# attinier84-2digit-shield-mk-1_0.net
KiCad netlist of a schematic drawn in EAGLE
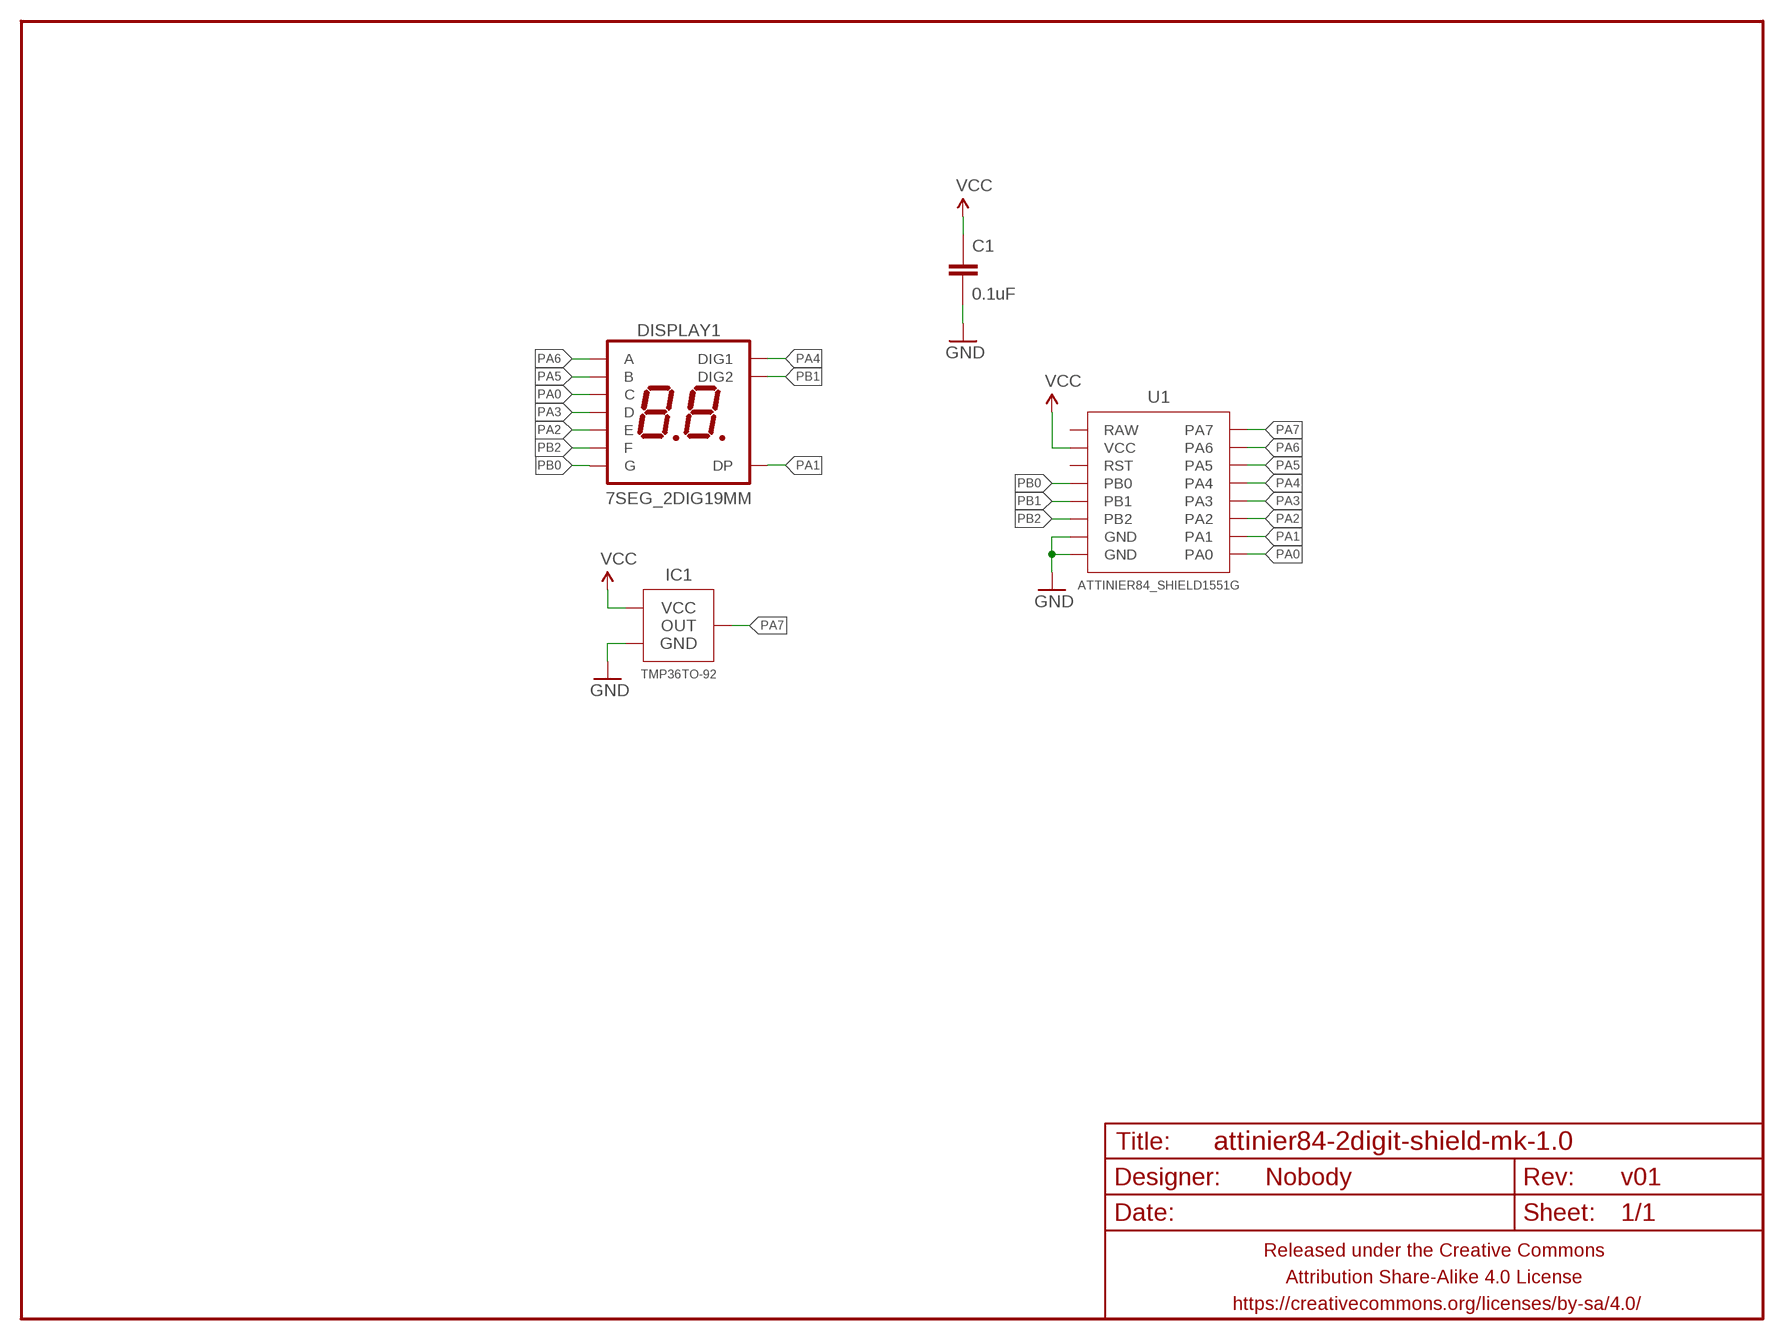
[diagram p0: schematic, sheet 1]

(export (version "E")
  (design (tool "Eeschema 10.0.6"))
  (components
    (comp (ref "C1")
      (value "0.1uF")
      (footprint "eagle-import:C025-024X044")
      (libsource (lib "eagle-import") (part "CAPACITOR-CERAMIC025-024X044"))
    )
    (comp (ref "DISPLAY1")
      (value "7SEG_2DIG19MM")
      (footprint "eagle-import:7SEG_2DIG_19MM")
      (libsource (lib "eagle-import") (part "7SEG_2DIG19MM"))
    )
    (comp (ref "FRAME1")
      (value "FRAME-LETTERNO_PACKAGE")
      (footprint "eagle-import:DUMMY")
      (fields (field (name "DESIGNER") "Nobody"))
      (libsource (lib "eagle-import") (part "FRAME-LETTERNO_PACKAGE"))
    )
    (comp (ref "IC1")
      (value "TMP36TO-92")
      (footprint "eagle-import:TO-92-AMMO")
      (libsource (lib "eagle-import") (part "TMP36TO-92"))
    )
    (comp (ref "U1")
      (value "ATTINIER84_SHIELD1551G")
      (footprint "eagle-import:ATTINIER84_SHIELD2")
      (libsource (lib "eagle-import") (part "ATTINIER84_SHIELD1551G"))
    )
  )
  (nets
    (net (code "1") (name "GND") (class "Default")
      (node (ref "C1") (pin "2") (pinfunction "2_2") (pintype "passive"))
      (node (ref "IC1") (pin "3") (pinfunction "GND_3") (pintype "bidirectional"))
      (node (ref "U1") (pin "GND@1") (pinfunction "GND_GND@1") (pintype "bidirectional"))
      (node (ref "U1") (pin "GND@2") (pinfunction "GND_GND@2") (pintype "bidirectional"))
    )
    (net (code "2") (name "PA0") (class "Default")
      (node (ref "DISPLAY1") (pin "1") (pinfunction "C_1") (pintype "passive"))
      (node (ref "U1") (pin "PA0") (pinfunction "PA0_PA0") (pintype "bidirectional"))
    )
    (net (code "3") (name "PA1") (class "Default")
      (node (ref "DISPLAY1") (pin "2") (pinfunction "DP_2") (pintype "passive"))
      (node (ref "U1") (pin "PA1") (pinfunction "PA1_PA1") (pintype "bidirectional"))
    )
    (net (code "4") (name "PA2") (class "Default")
      (node (ref "DISPLAY1") (pin "3") (pinfunction "E_3") (pintype "passive"))
      (node (ref "U1") (pin "PA2") (pinfunction "PA2_PA2") (pintype "bidirectional"))
    )
    (net (code "5") (name "PA3") (class "Default")
      (node (ref "DISPLAY1") (pin "4") (pinfunction "D_4") (pintype "passive"))
      (node (ref "U1") (pin "PA3") (pinfunction "PA3_PA3") (pintype "bidirectional"))
    )
    (net (code "6") (name "PA4") (class "Default")
      (node (ref "DISPLAY1") (pin "8") (pinfunction "DIG1_8") (pintype "passive"))
      (node (ref "U1") (pin "PA4") (pinfunction "PA4_PA4") (pintype "bidirectional"))
    )
    (net (code "7") (name "PA5") (class "Default")
      (node (ref "DISPLAY1") (pin "9") (pinfunction "B_9") (pintype "passive"))
      (node (ref "U1") (pin "PA5") (pinfunction "PA5_PA5") (pintype "bidirectional"))
    )
    (net (code "8") (name "PA6") (class "Default")
      (node (ref "DISPLAY1") (pin "10") (pinfunction "A_10") (pintype "passive"))
      (node (ref "U1") (pin "PA6") (pinfunction "PA6_PA6") (pintype "bidirectional"))
    )
    (net (code "9") (name "PA7") (class "Default")
      (node (ref "IC1") (pin "2") (pinfunction "OUT_2") (pintype "bidirectional"))
      (node (ref "U1") (pin "PA7") (pinfunction "PA7_PA7") (pintype "bidirectional"))
    )
    (net (code "10") (name "PB0") (class "Default")
      (node (ref "DISPLAY1") (pin "5") (pinfunction "G_5") (pintype "passive"))
      (node (ref "U1") (pin "PB0") (pinfunction "PB0_PB0") (pintype "bidirectional"))
    )
    (net (code "11") (name "PB1") (class "Default")
      (node (ref "DISPLAY1") (pin "7") (pinfunction "DIG2_7") (pintype "passive"))
      (node (ref "U1") (pin "PB1") (pinfunction "PB1_PB1") (pintype "bidirectional"))
    )
    (net (code "12") (name "PB2") (class "Default")
      (node (ref "DISPLAY1") (pin "6") (pinfunction "F_6") (pintype "passive"))
      (node (ref "U1") (pin "PB2") (pinfunction "PB2_PB2") (pintype "bidirectional"))
    )
    (net (code "13") (name "VCC") (class "Default")
      (node (ref "C1") (pin "1") (pinfunction "1_1") (pintype "passive"))
      (node (ref "IC1") (pin "1") (pinfunction "VCC_1") (pintype "bidirectional"))
      (node (ref "U1") (pin "VCC") (pinfunction "VCC_VCC") (pintype "bidirectional"))
    )
    (net (code "14") (name "unconnected-(U1-PadRAW)") (class "Default")
      (node (ref "U1") (pin "RAW") (pinfunction "RAW_RAW") (pintype "bidirectional"))
    )
    (net (code "15") (name "unconnected-(U1-PadRST)") (class "Default")
      (node (ref "U1") (pin "RST") (pinfunction "RST_RST") (pintype "bidirectional"))
    )
  )
)
